# VentaConnected_Arduino_V0_01_2017-12-03.net
KiCad netlist of a schematic drawn in EAGLE
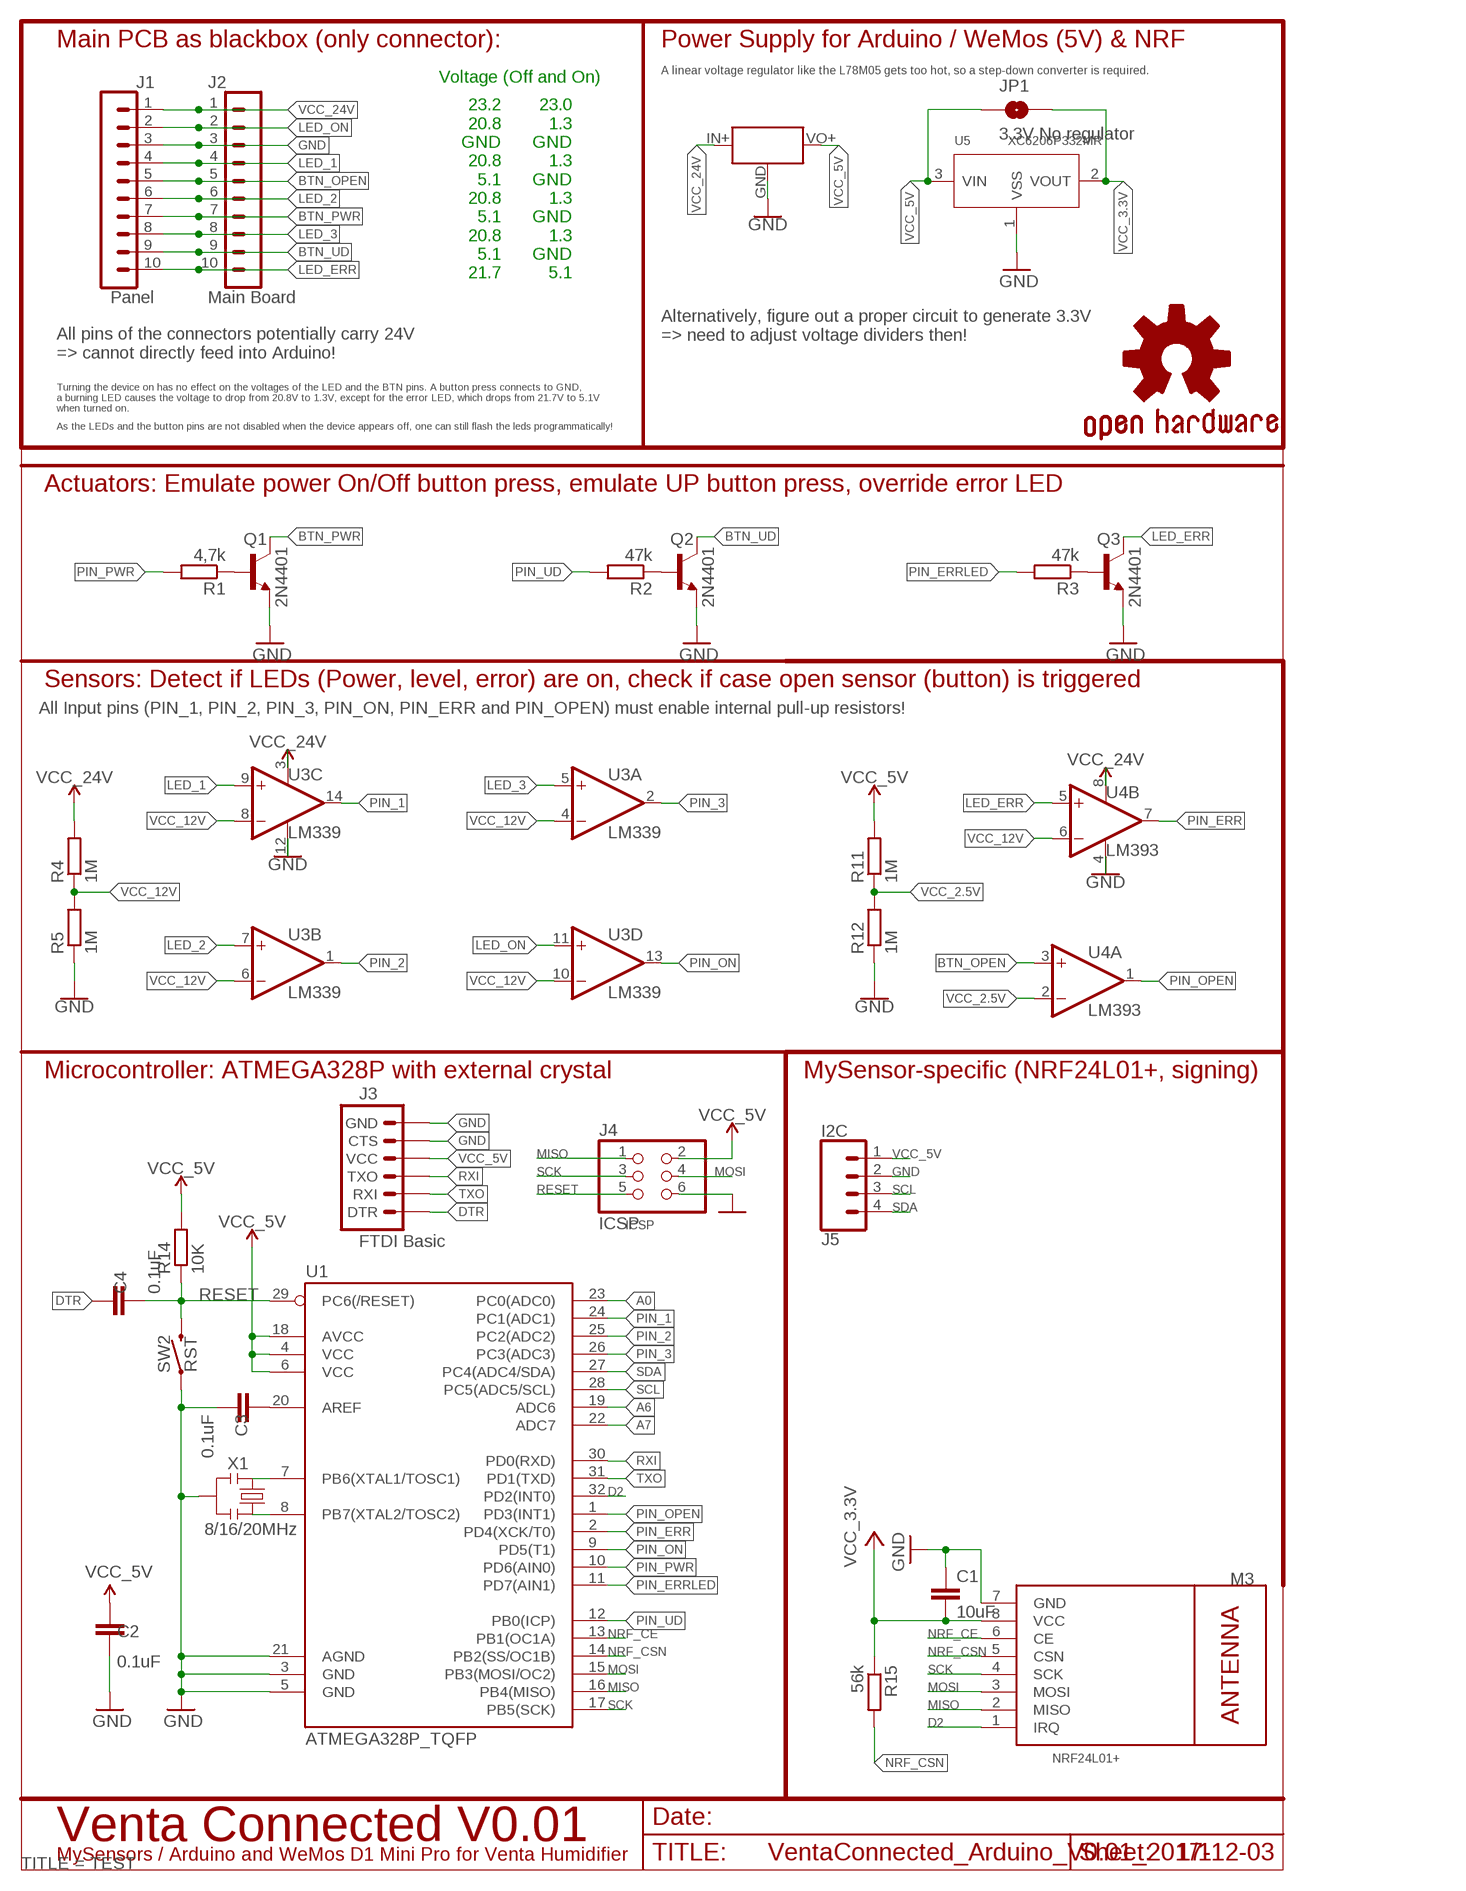
[diagram p0: schematic, sheet 1]

(export (version "E")
  (design (tool "Eeschema 10.0.6"))
  (components
    (comp (ref "C1")
      (value "10uF")
      (footprint "eagle-import:C0805")
      (libsource (lib "eagle-import") (part "C-EUC0805"))
    )
    (comp (ref "C2")
      (value "0.1uF")
      (footprint "eagle-import:C0805")
      (libsource (lib "eagle-import") (part "resistor_348_C-EUC0805"))
    )
    (comp (ref "C3")
      (value "0.1uF")
      (footprint "eagle-import:C0805")
      (libsource (lib "eagle-import") (part "resistor_348_C-EUC0805"))
    )
    (comp (ref "C4")
      (value "0.1uF")
      (footprint "eagle-import:C0805")
      (libsource (lib "eagle-import") (part "resistor_348_C-EUC0805"))
    )
    (comp (ref "GOLD_ORB_SM1")
      (value "OSHWLOGO_GOLD_ORB_SM")
      (footprint "eagle-import:OSHW2")
      (libsource (lib "eagle-import") (part "OSHWLOGO_GOLD_ORB_SM"))
    )
    (comp (ref "J1")
      (value "Panel")
      (footprint "eagle-import:2X5-SHROUDED")
      (libsource (lib "eagle-import") (part "CONN_05X2SHD"))
    )
    (comp (ref "J2")
      (value "Main Board")
      (footprint "eagle-import:2X5")
      (libsource (lib "eagle-import") (part "CONN_05X2PTH"))
    )
    (comp (ref "J3")
      (value "FTDI Basic")
      (footprint "eagle-import:1X06")
      (libsource (lib "eagle-import") (part "ARDUINO_SERIAL_PROGRAMPTH"))
    )
    (comp (ref "J4")
      (value "ICSP")
      (footprint "eagle-import:2X03")
      (libsource (lib "eagle-import") (part "PINHD-2X3"))
    )
    (comp (ref "J5")
      (value "I2C")
      (footprint "eagle-import:1X04")
      (libsource (lib "eagle-import") (part "CONN_04"))
    )
    (comp (ref "JP1")
      (value "3.3V No regulator")
      (footprint "eagle-import:SMT-JUMPER_2_NO_SILK")
      (libsource (lib "eagle-import") (part "JUMPER-SMT_2_NO_SILK"))
    )
    (comp (ref "M3")
      (value "NRF24L01+")
      (footprint "eagle-import:WIRELESS-NRF24L01-SMD")
      (libsource (lib "eagle-import") (part "WIRELESS-NRF24L01SMD"))
    )
    (comp (ref "Q1")
      (value "2N4401")
      (footprint "eagle-import:SOT23-BEC")
      (libsource (lib "eagle-import") (part "-NPN-SOT23-BECMMBT4401LT1"))
    )
    (comp (ref "Q2")
      (value "2N4401")
      (footprint "eagle-import:SOT23-BEC")
      (libsource (lib "eagle-import") (part "-NPN-SOT23-BECMMBT4401LT1"))
    )
    (comp (ref "Q3")
      (value "2N4401")
      (footprint "eagle-import:SOT23-BEC")
      (libsource (lib "eagle-import") (part "-NPN-SOT23-BECMMBT4401LT1"))
    )
    (comp (ref "R1")
      (value "4,7k")
      (footprint "eagle-import:R0805")
      (libsource (lib "eagle-import") (part "resistor_348_R-EU_R0805"))
    )
    (comp (ref "R2")
      (value "47k")
      (footprint "eagle-import:R0805")
      (libsource (lib "eagle-import") (part "resistor_348_R-EU_R0805"))
    )
    (comp (ref "R3")
      (value "47k")
      (footprint "eagle-import:R0805")
      (libsource (lib "eagle-import") (part "resistor_348_R-EU_R0805"))
    )
    (comp (ref "R4")
      (value "1M")
      (footprint "eagle-import:R0805")
      (libsource (lib "eagle-import") (part "resistor_348_R-EU_R0805"))
    )
    (comp (ref "R5")
      (value "1M")
      (footprint "eagle-import:R0805")
      (libsource (lib "eagle-import") (part "resistor_348_R-EU_R0805"))
    )
    (comp (ref "R11")
      (value "1M")
      (footprint "eagle-import:R0805")
      (libsource (lib "eagle-import") (part "resistor_348_R-EU_R0805"))
    )
    (comp (ref "R12")
      (value "1M")
      (footprint "eagle-import:R0805")
      (libsource (lib "eagle-import") (part "resistor_348_R-EU_R0805"))
    )
    (comp (ref "R14")
      (value "10K")
      (footprint "eagle-import:R0805")
      (libsource (lib "eagle-import") (part "rcl_334_R-EU_R0805"))
    )
    (comp (ref "R15")
      (value "56k")
      (footprint "eagle-import:R0805")
      (libsource (lib "eagle-import") (part "R-EU_R0805"))
    )
    (comp (ref "SW2")
      (value "RST")
      (footprint "eagle-import:TACTILE_SWITCH_SMD_6.0X3.5MM")
      (libsource (lib "eagle-import") (part "MOMENTARY-SWITCH-SPST-SMD-6.0X3.5MM"))
    )
    (comp (ref "U1")
      (value "ATMEGA328P_TQFP")
      (footprint "eagle-import:TQFP32-08")
      (libsource (lib "eagle-import") (part "ATMEGA328P_TQFP"))
    )
    (comp (ref "U2")
      (value "MINI_BUCK_CONVERTER_UPSIDEDOWN")
      (footprint "eagle-import:MINI_BUCK_CONVERTER_UPDOWN")
      (libsource (lib "eagle-import") (part "MINI_BUCK_CONVERTER_UPSIDEDOWN"))
    )
    (comp (ref "U3")
      (value "LM339")
      (footprint "eagle-import:SO14")
      (libsource (lib "eagle-import") (part "TLC339D"))
    )
    (comp (ref "U4")
      (value "LM393")
      (footprint "eagle-import:SO08")
      (libsource (lib "eagle-import") (part "LM393D"))
    )
    (comp (ref "U5")
      (value "XC6206P332MR")
      (footprint "eagle-import:SOT-23")
      (fields (field (name "MPN") "XC6206P332MR-G"))
      (libsource (lib "eagle-import") (part "PMIC-LDO-XC6206P332MR-G(SOT23)"))
    )
    (comp (ref "X1")
      (value "8/16/20MHz")
      (footprint "eagle-import:RESONATOR-SMD-1_1")
      (libsource (lib "eagle-import") (part "RESONATOR1{colon}1"))
    )
  )
  (nets
    (net (code "1") (name "/D2") (class "Default")
      (node (ref "M3") (pin "1") (pinfunction "IRQ_1") (pintype "bidirectional"))
      (node (ref "U1") (pin "32") (pinfunction "PD2(INT0)_32") (pintype "bidirectional"))
    )
    (net (code "2") (name "/MISO") (class "Default")
      (node (ref "J4") (pin "1") (pinfunction "1_1") (pintype "passive"))
      (node (ref "M3") (pin "2") (pinfunction "MISO_2") (pintype "bidirectional"))
      (node (ref "U1") (pin "16") (pinfunction "PB4(MISO)_16") (pintype "bidirectional"))
    )
    (net (code "3") (name "/MOSI") (class "Default")
      (node (ref "J4") (pin "4") (pinfunction "4_4") (pintype "passive"))
      (node (ref "M3") (pin "3") (pinfunction "MOSI_3") (pintype "bidirectional"))
      (node (ref "U1") (pin "15") (pinfunction "PB3(MOSI/OC2)_15") (pintype "bidirectional"))
    )
    (net (code "4") (name "/NRF_CE") (class "Default")
      (node (ref "M3") (pin "6") (pinfunction "CE_6") (pintype "bidirectional"))
      (node (ref "U1") (pin "13") (pinfunction "PB1(OC1A)_13") (pintype "bidirectional"))
    )
    (net (code "5") (name "/RESET") (class "Default")
      (node (ref "C4") (pin "1") (pinfunction "1_1") (pintype "passive"))
      (node (ref "J4") (pin "5") (pinfunction "5_5") (pintype "passive"))
      (node (ref "R14") (pin "1") (pinfunction "1_1") (pintype "passive"))
      (node (ref "SW2") (pin "2") (pinfunction "2_2") (pintype "passive"))
      (node (ref "U1") (pin "29") (pinfunction "PC6(/RESET)_29") (pintype "bidirectional"))
    )
    (net (code "6") (name "/SCK") (class "Default")
      (node (ref "J4") (pin "3") (pinfunction "3_3") (pintype "passive"))
      (node (ref "M3") (pin "4") (pinfunction "SCK_4") (pintype "bidirectional"))
      (node (ref "U1") (pin "17") (pinfunction "PB5(SCK)_17") (pintype "bidirectional"))
    )
    (net (code "7") (name "A0") (class "Default")
      (node (ref "U1") (pin "23") (pinfunction "PC0(ADC0)_23") (pintype "bidirectional"))
    )
    (net (code "8") (name "A6") (class "Default")
      (node (ref "U1") (pin "19") (pinfunction "ADC6_19") (pintype "bidirectional"))
    )
    (net (code "9") (name "A7") (class "Default")
      (node (ref "U1") (pin "22") (pinfunction "ADC7_22") (pintype "bidirectional"))
    )
    (net (code "10") (name "BTN_OPEN") (class "Default")
      (node (ref "J1") (pin "5") (pinfunction "5_5") (pintype "passive"))
      (node (ref "J2") (pin "5") (pinfunction "5_5") (pintype "passive"))
      (node (ref "U4") (pin "3") (pinfunction "+IN_3") (pintype "input"))
    )
    (net (code "11") (name "BTN_PWR") (class "Default")
      (node (ref "J1") (pin "7") (pinfunction "7_7") (pintype "passive"))
      (node (ref "J2") (pin "7") (pinfunction "7_7") (pintype "passive"))
      (node (ref "Q1") (pin "C") (pinfunction "C_C") (pintype "passive"))
    )
    (net (code "12") (name "BTN_UD") (class "Default")
      (node (ref "J1") (pin "9") (pinfunction "9_9") (pintype "passive"))
      (node (ref "J2") (pin "9") (pinfunction "9_9") (pintype "passive"))
      (node (ref "Q2") (pin "C") (pinfunction "C_C") (pintype "passive"))
    )
    (net (code "13") (name "DTR") (class "Default")
      (node (ref "C4") (pin "2") (pinfunction "2_2") (pintype "passive"))
      (node (ref "J3") (pin "1") (pinfunction "DTR_1") (pintype "passive"))
    )
    (net (code "14") (name "GND") (class "Default")
      (node (ref "C1") (pin "1") (pinfunction "1_1") (pintype "passive"))
      (node (ref "C2") (pin "1") (pinfunction "1_1") (pintype "passive"))
      (node (ref "C3") (pin "1") (pinfunction "1_1") (pintype "passive"))
      (node (ref "J1") (pin "3") (pinfunction "3_3") (pintype "passive"))
      (node (ref "J2") (pin "3") (pinfunction "3_3") (pintype "passive"))
      (node (ref "J3") (pin "5") (pinfunction "CTS_5") (pintype "passive"))
      (node (ref "J3") (pin "6") (pinfunction "GND_6") (pintype "passive"))
      (node (ref "J4") (pin "6") (pinfunction "6_6") (pintype "passive"))
      (node (ref "J5") (pin "2") (pinfunction "2_2") (pintype "passive"))
      (node (ref "M3") (pin "7") (pinfunction "GND_7") (pintype "power_in"))
      (node (ref "Q1") (pin "E") (pinfunction "E_E") (pintype "passive"))
      (node (ref "Q2") (pin "E") (pinfunction "E_E") (pintype "passive"))
      (node (ref "Q3") (pin "E") (pinfunction "E_E") (pintype "passive"))
      (node (ref "R12") (pin "1") (pinfunction "1_1") (pintype "passive"))
      (node (ref "R5") (pin "1") (pinfunction "1_1") (pintype "passive"))
      (node (ref "SW2") (pin "1") (pinfunction "1_1") (pintype "passive"))
      (node (ref "U1") (pin "21") (pinfunction "AGND_21") (pintype "bidirectional"))
      (node (ref "U1") (pin "3") (pinfunction "GND_3") (pintype "bidirectional"))
      (node (ref "U1") (pin "5") (pinfunction "GND_5") (pintype "bidirectional"))
      (node (ref "U2") (pin "GND") (pinfunction "GND_GND") (pintype "bidirectional"))
      (node (ref "U3") (pin "12") (pinfunction "V-_12") (pintype "power_in"))
      (node (ref "U4") (pin "4") (pinfunction "V-_4") (pintype "power_in"))
      (node (ref "U5") (pin "1") (pinfunction "VSS_1") (pintype "power_in"))
      (node (ref "X1") (pin "2") (pinfunction "2_2") (pintype "passive"))
    )
    (net (code "15") (name "LED_1") (class "Default")
      (node (ref "J1") (pin "4") (pinfunction "4_4") (pintype "passive"))
      (node (ref "J2") (pin "4") (pinfunction "4_4") (pintype "passive"))
      (node (ref "U3") (pin "9") (pinfunction "+IN_9") (pintype "input"))
    )
    (net (code "16") (name "LED_2") (class "Default")
      (node (ref "J1") (pin "6") (pinfunction "6_6") (pintype "passive"))
      (node (ref "J2") (pin "6") (pinfunction "6_6") (pintype "passive"))
      (node (ref "U3") (pin "7") (pinfunction "+IN_7") (pintype "input"))
    )
    (net (code "17") (name "LED_3") (class "Default")
      (node (ref "J1") (pin "8") (pinfunction "8_8") (pintype "passive"))
      (node (ref "J2") (pin "8") (pinfunction "8_8") (pintype "passive"))
      (node (ref "U3") (pin "5") (pinfunction "+IN_5") (pintype "input"))
    )
    (net (code "18") (name "LED_ERR") (class "Default")
      (node (ref "J1") (pin "10") (pinfunction "10_10") (pintype "passive"))
      (node (ref "J2") (pin "10") (pinfunction "10_10") (pintype "passive"))
      (node (ref "Q3") (pin "C") (pinfunction "C_C") (pintype "passive"))
      (node (ref "U4") (pin "5") (pinfunction "+IN_5") (pintype "input"))
    )
    (net (code "19") (name "LED_ON") (class "Default")
      (node (ref "J1") (pin "2") (pinfunction "2_2") (pintype "passive"))
      (node (ref "J2") (pin "2") (pinfunction "2_2") (pintype "passive"))
      (node (ref "U3") (pin "11") (pinfunction "+IN_11") (pintype "input"))
    )
    (net (code "20") (name "NRF_CSN") (class "Default")
      (node (ref "M3") (pin "5") (pinfunction "CSN_5") (pintype "bidirectional"))
      (node (ref "R15") (pin "2") (pinfunction "2_2") (pintype "passive"))
      (node (ref "U1") (pin "14") (pinfunction "PB2(SS/OC1B)_14") (pintype "bidirectional"))
    )
    (net (code "21") (name "Net-(Q1-PadB)") (class "Default")
      (node (ref "Q1") (pin "B") (pinfunction "B_B") (pintype "passive"))
      (node (ref "R1") (pin "1") (pinfunction "1_1") (pintype "passive"))
    )
    (net (code "22") (name "Net-(Q2-PadB)") (class "Default")
      (node (ref "Q2") (pin "B") (pinfunction "B_B") (pintype "passive"))
      (node (ref "R2") (pin "1") (pinfunction "1_1") (pintype "passive"))
    )
    (net (code "23") (name "Net-(Q3-PadB)") (class "Default")
      (node (ref "Q3") (pin "B") (pinfunction "B_B") (pintype "passive"))
      (node (ref "R3") (pin "1") (pinfunction "1_1") (pintype "passive"))
    )
    (net (code "24") (name "Net-(U1-AREF)") (class "Default")
      (node (ref "C3") (pin "2") (pinfunction "2_2") (pintype "passive"))
      (node (ref "U1") (pin "20") (pinfunction "AREF_20") (pintype "bidirectional"))
    )
    (net (code "25") (name "Net-(U1-PB6(XTAL1{slash}TOSC1))") (class "Default")
      (node (ref "U1") (pin "7") (pinfunction "PB6(XTAL1/TOSC1)_7") (pintype "bidirectional"))
      (node (ref "X1") (pin "1") (pinfunction "1_1") (pintype "passive"))
    )
    (net (code "26") (name "Net-(U1-PB7(XTAL2{slash}TOSC2))") (class "Default")
      (node (ref "U1") (pin "8") (pinfunction "PB7(XTAL2/TOSC2)_8") (pintype "bidirectional"))
      (node (ref "X1") (pin "3") (pinfunction "3_3") (pintype "passive"))
    )
    (net (code "27") (name "PIN_1") (class "Default")
      (node (ref "U1") (pin "24") (pinfunction "PC1(ADC1)_24") (pintype "bidirectional"))
      (node (ref "U3") (pin "14") (pinfunction "OUT_14") (pintype "output"))
    )
    (net (code "28") (name "PIN_2") (class "Default")
      (node (ref "U1") (pin "25") (pinfunction "PC2(ADC2)_25") (pintype "bidirectional"))
      (node (ref "U3") (pin "1") (pinfunction "OUT_1") (pintype "output"))
    )
    (net (code "29") (name "PIN_3") (class "Default")
      (node (ref "U1") (pin "26") (pinfunction "PC3(ADC3)_26") (pintype "bidirectional"))
      (node (ref "U3") (pin "2") (pinfunction "OUT_2") (pintype "output"))
    )
    (net (code "30") (name "PIN_ERR") (class "Default")
      (node (ref "U1") (pin "2") (pinfunction "PD4(XCK/T0)_2") (pintype "bidirectional"))
      (node (ref "U4") (pin "7") (pinfunction "OUT_7") (pintype "output"))
    )
    (net (code "31") (name "PIN_ERRLED") (class "Default")
      (node (ref "R3") (pin "2") (pinfunction "2_2") (pintype "passive"))
      (node (ref "U1") (pin "11") (pinfunction "PD7(AIN1)_11") (pintype "bidirectional"))
    )
    (net (code "32") (name "PIN_ON") (class "Default")
      (node (ref "U1") (pin "9") (pinfunction "PD5(T1)_9") (pintype "bidirectional"))
      (node (ref "U3") (pin "13") (pinfunction "OUT_13") (pintype "output"))
    )
    (net (code "33") (name "PIN_OPEN") (class "Default")
      (node (ref "U1") (pin "1") (pinfunction "PD3(INT1)_1") (pintype "bidirectional"))
      (node (ref "U4") (pin "1") (pinfunction "OUT_1") (pintype "output"))
    )
    (net (code "34") (name "PIN_PWR") (class "Default")
      (node (ref "R1") (pin "2") (pinfunction "2_2") (pintype "passive"))
      (node (ref "U1") (pin "10") (pinfunction "PD6(AIN0)_10") (pintype "bidirectional"))
    )
    (net (code "35") (name "PIN_UD") (class "Default")
      (node (ref "R2") (pin "2") (pinfunction "2_2") (pintype "passive"))
      (node (ref "U1") (pin "12") (pinfunction "PB0(ICP)_12") (pintype "bidirectional"))
    )
    (net (code "36") (name "RXI") (class "Default")
      (node (ref "J3") (pin "3") (pinfunction "TXO_3") (pintype "passive"))
      (node (ref "U1") (pin "30") (pinfunction "PD0(RXD)_30") (pintype "bidirectional"))
    )
    (net (code "37") (name "SCL") (class "Default")
      (node (ref "J5") (pin "3") (pinfunction "3_3") (pintype "passive"))
      (node (ref "U1") (pin "28") (pinfunction "PC5(ADC5/SCL)_28") (pintype "bidirectional"))
    )
    (net (code "38") (name "SDA") (class "Default")
      (node (ref "J5") (pin "4") (pinfunction "4_4") (pintype "passive"))
      (node (ref "U1") (pin "27") (pinfunction "PC4(ADC4/SDA)_27") (pintype "bidirectional"))
    )
    (net (code "39") (name "TXO") (class "Default")
      (node (ref "J3") (pin "2") (pinfunction "RXI_2") (pintype "passive"))
      (node (ref "U1") (pin "31") (pinfunction "PD1(TXD)_31") (pintype "bidirectional"))
    )
    (net (code "40") (name "VCC_2.5V") (class "Default")
      (node (ref "R11") (pin "1") (pinfunction "1_1") (pintype "passive"))
      (node (ref "R12") (pin "2") (pinfunction "2_2") (pintype "passive"))
      (node (ref "U4") (pin "2") (pinfunction "-IN_2") (pintype "input"))
    )
    (net (code "41") (name "VCC_3.3V") (class "Default")
      (node (ref "C1") (pin "2") (pinfunction "2_2") (pintype "passive"))
      (node (ref "JP1") (pin "2") (pinfunction "2_2") (pintype "passive"))
      (node (ref "M3") (pin "8") (pinfunction "VCC_8") (pintype "power_in"))
      (node (ref "R15") (pin "1") (pinfunction "1_1") (pintype "passive"))
      (node (ref "U5") (pin "2") (pinfunction "VOUT_2") (pintype "output"))
    )
    (net (code "42") (name "VCC_5V") (class "Default")
      (node (ref "C2") (pin "2") (pinfunction "2_2") (pintype "passive"))
      (node (ref "J3") (pin "4") (pinfunction "VCC_4") (pintype "passive"))
      (node (ref "J4") (pin "2") (pinfunction "2_2") (pintype "passive"))
      (node (ref "J5") (pin "1") (pinfunction "1_1") (pintype "passive"))
      (node (ref "JP1") (pin "1") (pinfunction "1_1") (pintype "passive"))
      (node (ref "R11") (pin "2") (pinfunction "2_2") (pintype "passive"))
      (node (ref "R14") (pin "2") (pinfunction "2_2") (pintype "passive"))
      (node (ref "U1") (pin "18") (pinfunction "AVCC_18") (pintype "bidirectional"))
      (node (ref "U1") (pin "4") (pinfunction "VCC_4") (pintype "bidirectional"))
      (node (ref "U1") (pin "6") (pinfunction "VCC_6") (pintype "bidirectional"))
      (node (ref "U2") (pin "VO+") (pinfunction "VOUT_VO+") (pintype "power_in"))
      (node (ref "U5") (pin "3") (pinfunction "VIN_3") (pintype "input"))
    )
    (net (code "43") (name "VCC_12V") (class "Default")
      (node (ref "R4") (pin "1") (pinfunction "1_1") (pintype "passive"))
      (node (ref "R5") (pin "2") (pinfunction "2_2") (pintype "passive"))
      (node (ref "U3") (pin "10") (pinfunction "-IN_10") (pintype "input"))
      (node (ref "U3") (pin "4") (pinfunction "-IN_4") (pintype "input"))
      (node (ref "U3") (pin "6") (pinfunction "-IN_6") (pintype "input"))
      (node (ref "U3") (pin "8") (pinfunction "-IN_8") (pintype "input"))
      (node (ref "U4") (pin "6") (pinfunction "-IN_6") (pintype "input"))
    )
    (net (code "44") (name "VCC_24V") (class "Default")
      (node (ref "J1") (pin "1") (pinfunction "1_1") (pintype "passive"))
      (node (ref "J2") (pin "1") (pinfunction "1_1") (pintype "passive"))
      (node (ref "R4") (pin "2") (pinfunction "2_2") (pintype "passive"))
      (node (ref "U2") (pin "IN+") (pinfunction "VIN_IN+") (pintype "input"))
      (node (ref "U3") (pin "3") (pinfunction "V+_3") (pintype "power_in"))
      (node (ref "U4") (pin "8") (pinfunction "V+_8") (pintype "power_in"))
    )
  )
)
